# board.net
KiCad netlist of a schematic drawn in EAGLE
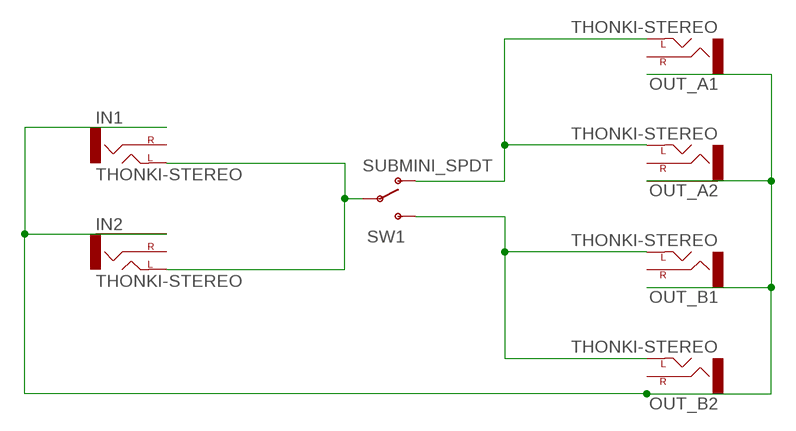
[diagram p0: schematic, sheet 1]

(export (version "E")
  (design (tool "Eeschema 10.0.6"))
  (components
    (comp (ref "IN1")
      (value "THONKI-STEREO")
      (footprint "eagle-import:WQP-PJ366ST_JACK")
      (libsource (lib "eagle-import") (part "THONKI-STEREO"))
    )
    (comp (ref "IN2")
      (value "THONKI-STEREO")
      (footprint "eagle-import:WQP-PJ366ST_JACK")
      (libsource (lib "eagle-import") (part "THONKI-STEREO"))
    )
    (comp (ref "OUT_A1")
      (value "THONKI-STEREO")
      (footprint "eagle-import:WQP-PJ366ST_JACK")
      (libsource (lib "eagle-import") (part "THONKI-STEREO"))
    )
    (comp (ref "OUT_A2")
      (value "THONKI-STEREO")
      (footprint "eagle-import:WQP-PJ366ST_JACK")
      (libsource (lib "eagle-import") (part "THONKI-STEREO"))
    )
    (comp (ref "OUT_B1")
      (value "THONKI-STEREO")
      (footprint "eagle-import:WQP-PJ366ST_JACK")
      (libsource (lib "eagle-import") (part "THONKI-STEREO"))
    )
    (comp (ref "OUT_B2")
      (value "THONKI-STEREO")
      (footprint "eagle-import:WQP-PJ366ST_JACK")
      (libsource (lib "eagle-import") (part "THONKI-STEREO"))
    )
    (comp (ref "SW1")
      (value "SUBMINI_SPDT")
      (footprint "eagle-import:SUBMINI_TOGGLE")
      (libsource (lib "eagle-import") (part "SUBMINI_SPDT"))
    )
  )
  (nets
    (net (code "1") (name "Net-(IN1-LEFT)") (class "Default")
      (node (ref "IN1") (pin "P$1_TIP") (pinfunction "LEFT_P$1_TIP") (pintype "bidirectional"))
      (node (ref "IN2") (pin "P$1_TIP") (pinfunction "LEFT_P$1_TIP") (pintype "bidirectional"))
      (node (ref "SW1") (pin "COM") (pinfunction "COMMON_COM") (pintype "passive"))
    )
    (net (code "2") (name "Net-(IN1-SLEEVE)") (class "Default")
      (node (ref "IN1") (pin "P$3_SLEEVE") (pinfunction "SLEEVE_P$3_SLEEVE") (pintype "bidirectional"))
      (node (ref "IN2") (pin "P$3_SLEEVE") (pinfunction "SLEEVE_P$3_SLEEVE") (pintype "bidirectional"))
      (node (ref "OUT_A1") (pin "P$3_SLEEVE") (pinfunction "SLEEVE_P$3_SLEEVE") (pintype "bidirectional"))
      (node (ref "OUT_A2") (pin "P$3_SLEEVE") (pinfunction "SLEEVE_P$3_SLEEVE") (pintype "bidirectional"))
      (node (ref "OUT_B1") (pin "P$3_SLEEVE") (pinfunction "SLEEVE_P$3_SLEEVE") (pintype "bidirectional"))
      (node (ref "OUT_B2") (pin "P$3_SLEEVE") (pinfunction "SLEEVE_P$3_SLEEVE") (pintype "bidirectional"))
    )
    (net (code "3") (name "Net-(OUT_A1-LEFT)") (class "Default")
      (node (ref "OUT_A1") (pin "P$1_TIP") (pinfunction "LEFT_P$1_TIP") (pintype "bidirectional"))
      (node (ref "OUT_A2") (pin "P$1_TIP") (pinfunction "LEFT_P$1_TIP") (pintype "bidirectional"))
      (node (ref "SW1") (pin "1") (pinfunction "O_1") (pintype "passive"))
    )
    (net (code "4") (name "Net-(OUT_B1-LEFT)") (class "Default")
      (node (ref "OUT_B1") (pin "P$1_TIP") (pinfunction "LEFT_P$1_TIP") (pintype "bidirectional"))
      (node (ref "OUT_B2") (pin "P$1_TIP") (pinfunction "LEFT_P$1_TIP") (pintype "bidirectional"))
      (node (ref "SW1") (pin "3") (pinfunction "S_3") (pintype "passive"))
    )
    (net (code "5") (name "unconnected-(IN1-RIGHT-PadP$2_SWITCH)") (class "Default")
      (node (ref "IN1") (pin "P$2_SWITCH") (pinfunction "RIGHT_P$2_SWITCH") (pintype "bidirectional"))
    )
    (net (code "6") (name "unconnected-(IN2-RIGHT-PadP$2_SWITCH)") (class "Default")
      (node (ref "IN2") (pin "P$2_SWITCH") (pinfunction "RIGHT_P$2_SWITCH") (pintype "bidirectional"))
    )
    (net (code "7") (name "unconnected-(OUT_A1-RIGHT-PadP$2_SWITCH)") (class "Default")
      (node (ref "OUT_A1") (pin "P$2_SWITCH") (pinfunction "RIGHT_P$2_SWITCH") (pintype "bidirectional"))
    )
    (net (code "8") (name "unconnected-(OUT_A2-RIGHT-PadP$2_SWITCH)") (class "Default")
      (node (ref "OUT_A2") (pin "P$2_SWITCH") (pinfunction "RIGHT_P$2_SWITCH") (pintype "bidirectional"))
    )
    (net (code "9") (name "unconnected-(OUT_B1-RIGHT-PadP$2_SWITCH)") (class "Default")
      (node (ref "OUT_B1") (pin "P$2_SWITCH") (pinfunction "RIGHT_P$2_SWITCH") (pintype "bidirectional"))
    )
    (net (code "10") (name "unconnected-(OUT_B2-RIGHT-PadP$2_SWITCH)") (class "Default")
      (node (ref "OUT_B2") (pin "P$2_SWITCH") (pinfunction "RIGHT_P$2_SWITCH") (pintype "bidirectional"))
    )
  )
)
